# ESP32-S3_module.net
KiCad netlist of a schematic drawn in Altium Designer
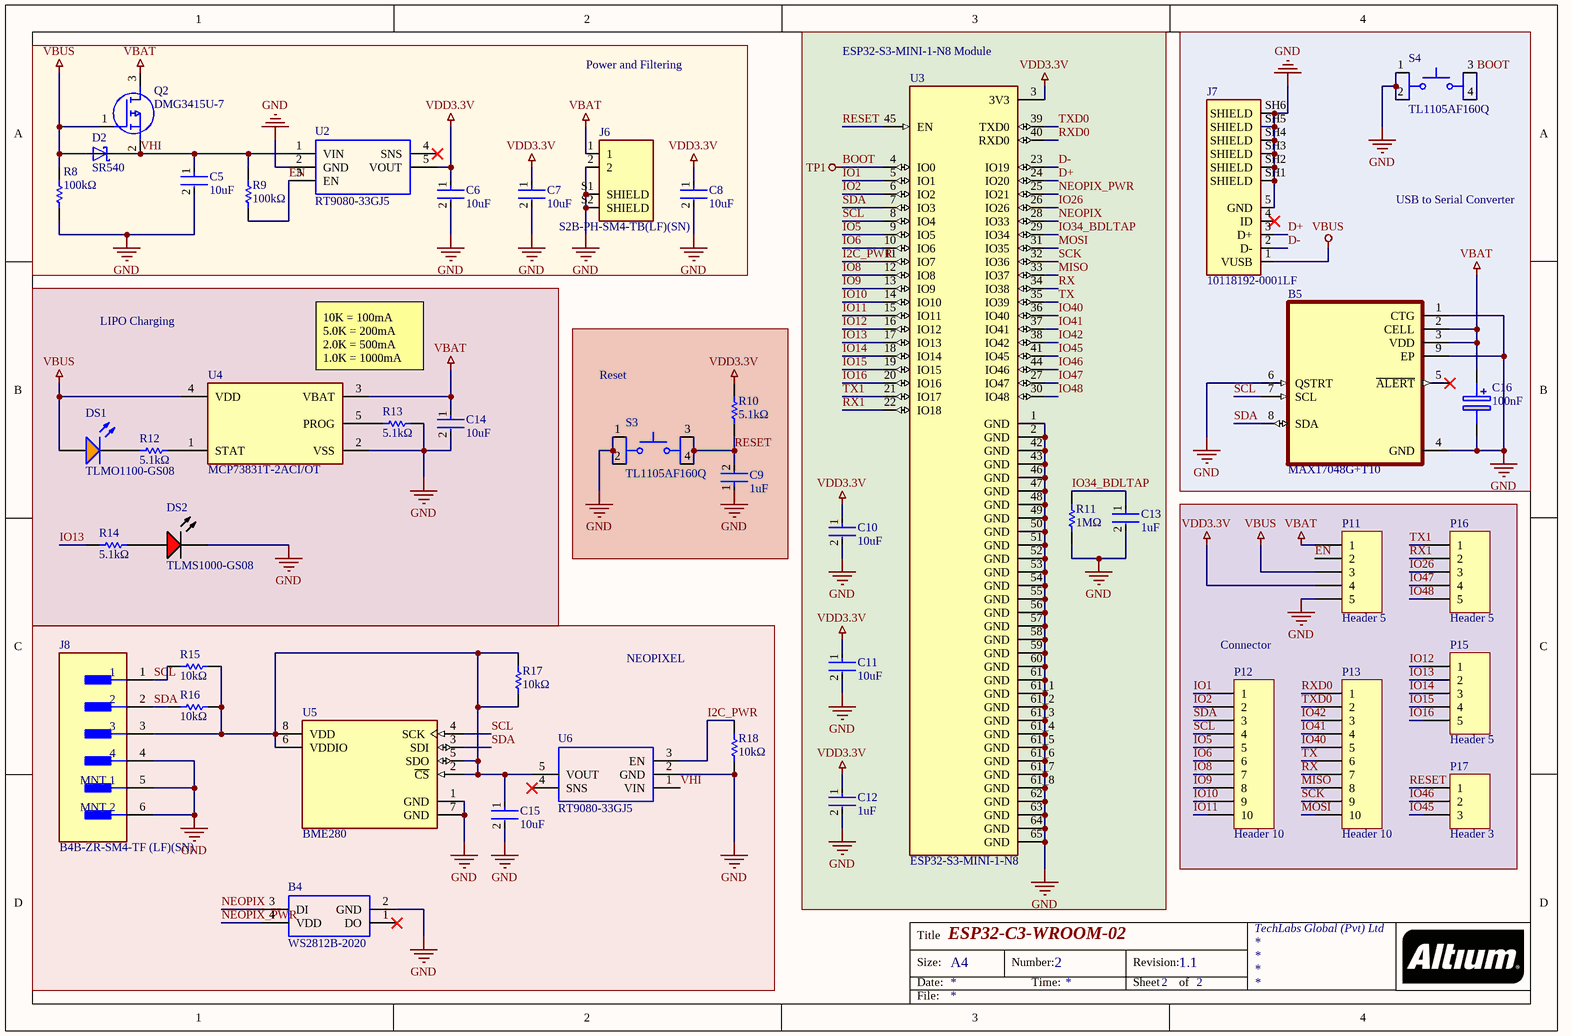
[diagram p0: ESP32-S3 module.SchDoc]

(export (version "E")
  (design (tool "Eeschema 10.0.6"))
  (components
    (comp (ref "B4")
      (value "WS2812B-2020")
      (footprint "WS2812B2020")
      (description "RGB SMD,2x2mm Light Emitting Diodes (LED) ROHS")
      (fields (field (name "MANUFACTURER") "Worldsemi") (field (name "LCSC PART #") "C965555"))
      (libsource (lib "WS2812B-2020") (part "WS2812B-2020"))
    )
    (comp (ref "B5")
      (value "MAX17048G+T10")
      (footprint "MAX17048G+T10")
      (description "Polymer 1 DFN-8-EP(2x2) Battery Management ICs ROHS")
      (fields
        (field (name "LCSC PART #") "C2682616")
        (field (name "MANUFACTURER") "Analog Devices Inc./Maxim Integrated")
      )
      (libsource (lib "MAX17048G+T10") (part "MAX17048G+T10"))
    )
    (comp (ref "C5")
      (value "10uF")
      (footprint "FP-CL10-IPC_C")
      (description "X5R 25V 10uF ±20% 0603 Multilayer Ceramic Capacitors MLCC - SMD/SMT ROHS")
      (fields (field (name "MFR. PART #") "CL10A106MA8NRNC") (field (name "LCSC PART #") "C96446"))
      (libsource (lib "Altium Content Vault") (part "b4654b650e69147ec39a6b967a45e02"))
    )
    (comp (ref "C6")
      (value "10uF")
      (footprint "FP-CL10-IPC_C")
      (description "X5R 25V 10uF ±20% 0603 Multilayer Ceramic Capacitors MLCC - SMD/SMT ROHS")
      (fields (field (name "MFR. PART #") "CL10A106MA8NRNC") (field (name "LCSC PART #") "C96446"))
      (libsource (lib "Altium Content Vault") (part "b4654b650e69147ec39a6b967a45e02"))
    )
    (comp (ref "C7")
      (value "10uF")
      (footprint "FP-CL10-IPC_C")
      (description "X5R 25V 10uF ±20% 0603 Multilayer Ceramic Capacitors MLCC - SMD/SMT ROHS")
      (fields (field (name "MFR. PART #") "CL10A106MA8NRNC") (field (name "LCSC PART #") "C96446"))
      (libsource (lib "Altium Content Vault") (part "b4654b650e69147ec39a6b967a45e02"))
    )
    (comp (ref "C8")
      (value "10uF")
      (footprint "FP-CL10-IPC_C")
      (description "X5R 25V 10uF ±20% 0603 Multilayer Ceramic Capacitors MLCC - SMD/SMT ROHS")
      (fields (field (name "MFR. PART #") "CL10A106MA8NRNC") (field (name "LCSC PART #") "C96446"))
      (libsource (lib "Altium Content Vault") (part "b4654b650e69147ec39a6b967a45e02"))
    )
    (comp (ref "C9")
      (value "1uF")
      (footprint "FP-CL10-IPC_A")
      (description "X5R 1uF 16V ±10% 0603 Multilayer Ceramic Capacitors MLCC - SMD/SMT ROHS")
      (fields (field (name "MANUFACTURER") "Samsung Electro-Mechanics") (field (name "LCSC PART #") "C1592"))
      (libsource (lib "Altium Content Vault") (part "b4654b650e69147ec39a6b967a45e02"))
    )
    (comp (ref "C10")
      (value "10uF")
      (footprint "FP-CL10-IPC_C")
      (description "X5R 25V 10uF ±20% 0603 Multilayer Ceramic Capacitors MLCC - SMD/SMT ROHS")
      (fields (field (name "MFR. PART #") "CL10A106MA8NRNC") (field (name "LCSC PART #") "C96446"))
      (libsource (lib "Altium Content Vault") (part "b4654b650e69147ec39a6b967a45e02"))
    )
    (comp (ref "C11")
      (value "10uF")
      (footprint "FP-CL10-IPC_C")
      (description "X5R 25V 10uF ±20% 0603 Multilayer Ceramic Capacitors MLCC - SMD/SMT ROHS")
      (fields (field (name "MFR. PART #") "CL10A106MA8NRNC") (field (name "LCSC PART #") "C96446"))
      (libsource (lib "Altium Content Vault") (part "b4654b650e69147ec39a6b967a45e02"))
    )
    (comp (ref "C12")
      (value "1uF")
      (footprint "FP-CL10-IPC_A")
      (description "X5R 1uF 16V ±10% 0603 Multilayer Ceramic Capacitors MLCC - SMD/SMT ROHS")
      (fields (field (name "LCSC PART #") "C1592") (field (name "MFR. PART #") "CL10A105KO8NNNC"))
      (libsource (lib "Altium Content Vault") (part "b4654b650e69147ec39a6b967a45e02"))
    )
    (comp (ref "C13")
      (value "1uF")
      (footprint "FP-CL10-IPC_A")
      (description "X5R 1uF 16V ±10% 0603 Multilayer Ceramic Capacitors MLCC - SMD/SMT ROHS")
      (fields (field (name "LCSC PART #") "C1592") (field (name "MFR. PART #") "CL10A105KO8NNNC"))
      (libsource (lib "Altium Content Vault") (part "b4654b650e69147ec39a6b967a45e02"))
    )
    (comp (ref "C14")
      (value "10uF")
      (footprint "FP-CL10-IPC_C")
      (description "X5R 25V 10uF ±20% 0603 Multilayer Ceramic Capacitors MLCC - SMD/SMT ROHS")
      (fields (field (name "MFR. PART #") "CL10A106MA8NRNC") (field (name "LCSC PART #") "C96446"))
      (libsource (lib "Altium Content Vault") (part "b4654b650e69147ec39a6b967a45e02"))
    )
    (comp (ref "C15")
      (value "10uF")
      (footprint "FP-CL10-IPC_C")
      (description "X5R 25V 10uF ±20% 0603 Multilayer Ceramic Capacitors MLCC - SMD/SMT ROHS")
      (fields (field (name "MFR. PART #") "CL10A106MA8NRNC") (field (name "LCSC PART #") "C96446"))
      (libsource (lib "Altium Content Vault") (part "b4654b650e69147ec39a6b967a45e02"))
    )
    (comp (ref "C16")
      (value "100nF")
      (footprint "T491A")
      (description "100nF 35V 20Ω@100kHz ±10% CASE-A-3216 Tantalum Capacitors ROHS")
      (fields (field (name "LCSC PART #") "C122257") (field (name "MFR. PART #") "T491A104K035AT"))
      (libsource (lib "T491A104K035AT") (part "T491A104K035AT"))
    )
    (comp (ref "D2")
      (value "SR540")
      (footprint "MBR540-DO-201AD")
      (description "40V 550mV@5A 5A DO-201AD Schottky Barrier Diodes (SBD) ROHS")
      (fields (field (name "MANUFACTURER") "DIYI Elec Tech") (field (name "LCSC PART #") "C129837"))
      (libsource (lib "MBR540-DO-201AD") (part "MBR540-DO-201AD"))
    )
    (comp (ref "DS1")
      (value "TLMO1100-GS08")
      (footprint "VISH-TLMX1100-2_V")
      (description "0603 Light Emitting Diodes (LED) ROHS")
      (fields (field (name "MANUFACTURER") "Vishay Intertech") (field (name "LCSC PART #") "C3148192"))
      (libsource (lib "Altium Content Vault") (part "LED-ORANGE-AK-2"))
    )
    (comp (ref "DS2")
      (value "TLMS1000-GS08")
      (footprint "VISH-TLMS1000_V")
      (description "Red 0603 Light Emitting Diodes (LED) ROHS")
      (fields (field (name "LCSC PART #") "C241893") (field (name "MANUFACTURER") "Vishay Intertech"))
      (libsource (lib "Altium Content Vault") (part "LED-RED-AK-2"))
    )
    (comp (ref "J6")
      (value "S2B-PH-SM4-TB(LF)(SN)")
      (footprint "JST_S2B-PH-SM4-TB(LF)(SN)")
      (fields (field (name "MANUFACTURER") "JST Sales America") (field (name "LCSC PART #") "C295747"))
      (libsource (lib "S2B-PH-SM4-TB(LF)(SN)") (part "S2B-PH-SM4-TB(LF)(SN)"))
    )
    (comp (ref "J7")
      (value "10118192-0001LF")
      (footprint "AMPHENOL_10118192-0001LF")
      (description "Single Port 5 Contact Horizontal Right Angle Shielded Micro B USB 2.0 Connector")
      (fields (field (name "LCSC PART #") "C132564") (field (name "MANUFACTURER") "Amphenol ICC"))
      (libsource (lib "10118192-0001LF") (part "10118192-0001LF"))
    )
    (comp (ref "J8")
      (value "B4B-ZR-SM4-TF (LF)(SN)")
      (footprint "FP-B4B-ZR-SM4-TF_LF_SN-MFG")
      (description "1x4P 1 1.5mm 4 Brass SMD,P=1.5mm Wire To Board / Wire To Wire Connector ROHS")
      (fields
        (field (name "MANUFACTURER") "JST Sales America")
        (field (name "MFR. PART #") "B4B-ZR-SM4-TF(LF)(SN)")
      )
      (libsource (lib "Altium Content Vault") (part "8e3688c4b118bffc0dd9b7401e414ba"))
    )
    (comp (ref "P11")
      (value "Header 5")
      (footprint "HDR1X5")
      (description "Header, 5-Pin")
      (fields (field (name "PUBLISHER") "Altium Limited"))
      (libsource (lib "Miscellaneous Connectors") (part "Header 5"))
    )
    (comp (ref "P12")
      (value "Header 10")
      (footprint "HDR1X10")
      (description "Header, 10-Pin")
      (fields (field (name "PUBLISHER") "Altium Limited"))
      (libsource (lib "Miscellaneous Connectors") (part "Header 10"))
    )
    (comp (ref "P13")
      (value "Header 10")
      (footprint "HDR1X10")
      (description "Header, 10-Pin")
      (fields (field (name "PUBLISHER") "Altium Limited"))
      (libsource (lib "Miscellaneous Connectors") (part "Header 10"))
    )
    (comp (ref "P15")
      (value "Header 5")
      (footprint "HDR1X5")
      (description "Header, 5-Pin")
      (fields (field (name "PUBLISHER") "Altium Limited"))
      (libsource (lib "Miscellaneous Connectors") (part "Header 5"))
    )
    (comp (ref "P16")
      (value "Header 5")
      (footprint "HDR1X5")
      (description "Header, 5-Pin")
      (fields (field (name "PUBLISHER") "Altium Limited"))
      (libsource (lib "Miscellaneous Connectors") (part "Header 5"))
    )
    (comp (ref "P17")
      (value "Header 3")
      (footprint "HDR1X3")
      (description "Header, 3-Pin")
      (fields (field (name "PUBLISHER") "Altium Limited"))
      (libsource (lib "Miscellaneous Connectors") (part "Header 3"))
    )
    (comp (ref "Q2")
      (value "DMG3415U-7")
      (footprint "SOT96P240X120-3N")
      (description "20V 4A 39mΩ@4.5V,4A 900mW P Channel SOT-23 MOSFETs ROHS")
      (fields (field (name "MANUFACTURER") "Diodes Incorporated") (field (name "LCSC PART #") "C96616"))
      (libsource (lib "DMG3415U-7") (part "DMG3415U-7"))
    )
    (comp (ref "R8")
      (value "100kΩ")
      (footprint "RESC1005X40X25NL05T10")
      (description "62.5mW 100kΩ ±1% Thick Film Resistors 0402 Chip Resistor - Surface Mount ROHS")
      (fields (field (name "MFR. PART #") "RC0402FR-07100KL") (field (name "MANUFACTURER") "YAGEO"))
      (libsource (lib "Altium Content Vault") (part "RES"))
    )
    (comp (ref "R9")
      (value "100kΩ")
      (footprint "RESC1005X40X25NL05T10")
      (description "62.5mW 100kΩ ±1% Thick Film Resistors 0402 Chip Resistor - Surface Mount ROHS")
      (fields (field (name "MFR. PART #") "RC0402FR-07100KL") (field (name "MANUFACTURER") "YAGEO"))
      (libsource (lib "Altium Content Vault") (part "RES"))
    )
    (comp (ref "R10")
      (value "5.1kΩ")
      (footprint "RESC1005X40X25NL05T10")
      (description "62.5mW Thick Film Resistors ±1% 5.1kΩ 0402 Chip Resistor - Surface Mount ROHS")
      (fields (field (name "MFR. PART #") "RC0402FR-075K1L") (field (name "MANUFACTURER") "YAGEO"))
      (libsource (lib "Altium Content Vault") (part "RES"))
    )
    (comp (ref "R11")
      (value "1MΩ")
      (footprint "RESC1005X40X25NL05T10")
      (description "62.5mW Thick Film Resistors ±1% 1MΩ 0402 Chip Resistor - Surface Mount ROHS")
      (fields (field (name "MFR. PART #") "RC0402FR-071ML") (field (name "LCSC PART #") "C138033"))
      (libsource (lib "Altium Content Vault") (part "RES"))
    )
    (comp (ref "R12")
      (value "5.1kΩ")
      (footprint "RESC1005X40X25NL05T10")
      (description "62.5mW Thick Film Resistors ±1% 5.1kΩ 0402 Chip Resistor - Surface Mount ROHS")
      (fields (field (name "MFR. PART #") "RC0402FR-075K1L") (field (name "MANUFACTURER") "YAGEO"))
      (libsource (lib "Altium Content Vault") (part "RES"))
    )
    (comp (ref "R13")
      (value "5.1kΩ")
      (footprint "RESC1005X40X25NL05T10")
      (description "62.5mW Thick Film Resistors ±1% 5.1kΩ 0402 Chip Resistor - Surface Mount ROHS")
      (fields (field (name "MFR. PART #") "RC0402FR-075K1L") (field (name "MANUFACTURER") "YAGEO"))
      (libsource (lib "Altium Content Vault") (part "RES"))
    )
    (comp (ref "R14")
      (value "5.1kΩ")
      (footprint "RESC1005X40X25NL05T10")
      (description "62.5mW Thick Film Resistors ±1% 5.1kΩ 0402 Chip Resistor - Surface Mount ROHS")
      (fields (field (name "MFR. PART #") "RC0402FR-075K1L") (field (name "MANUFACTURER") "YAGEO"))
      (libsource (lib "Altium Content Vault") (part "RES"))
    )
    (comp (ref "R15")
      (value "10kΩ")
      (footprint "RESC1005X40X25LL05T10")
      (description "10kΩ Thick Film Resistors 62.5mW ±1% 0402 Chip Resistor - Surface Mount ROHS")
      (fields (field (name "MFR. PART #") "RC0402FR-0710KL") (field (name "MANUFACTURER") "YAGEO"))
      (libsource (lib "Altium Content Vault") (part "RES"))
    )
    (comp (ref "R16")
      (value "10kΩ")
      (footprint "RESC1005X40X25LL05T10")
      (description "10kΩ Thick Film Resistors 62.5mW ±1% 0402 Chip Resistor - Surface Mount ROHS")
      (fields (field (name "MFR. PART #") "RC0402FR-0710KL") (field (name "MANUFACTURER") "YAGEO"))
      (libsource (lib "Altium Content Vault") (part "RES"))
    )
    (comp (ref "R17")
      (value "10kΩ")
      (footprint "RESC1005X40X25LL05T10")
      (description "10kΩ Thick Film Resistors 62.5mW ±1% 0402 Chip Resistor - Surface Mount ROHS")
      (fields (field (name "MFR. PART #") "RC0402FR-0710KL") (field (name "MANUFACTURER") "YAGEO"))
      (libsource (lib "Altium Content Vault") (part "RES"))
    )
    (comp (ref "R18")
      (value "10kΩ")
      (footprint "RESC1005X40X25LL05T10")
      (description "10kΩ Thick Film Resistors 62.5mW ±1% 0402 Chip Resistor - Surface Mount ROHS")
      (fields (field (name "MFR. PART #") "RC0402FR-0710KL") (field (name "MANUFACTURER") "YAGEO"))
      (libsource (lib "Altium Content Vault") (part "RES"))
    )
    (comp (ref "S3")
      (value "TL1105AF160Q")
      (footprint "TL1105AF160Q")
      (description "6mm 1.4mm Round Button 50mA Straight 6mm SPST 12V Plugin,6x6mm Tactile Switches ROHS")
      (fields (field (name "MANUFACTURER") "E-Switch") (field (name "LCSC PART #") "C273465"))
      (libsource (lib "TL1105AF160Q") (part "TL1105AF160Q"))
    )
    (comp (ref "S4")
      (value "TL1105AF160Q")
      (footprint "TL1105AF160Q")
      (description "6mm 1.4mm Round Button 50mA Straight 6mm SPST 12V Plugin,6x6mm Tactile Switches ROHS")
      (fields (field (name "MANUFACTURER") "E-Switch") (field (name "LCSC PART #") "C273465"))
      (libsource (lib "TL1105AF160Q") (part "TL1105AF160Q"))
    )
    (comp (ref "U2")
      (value "RT9080-33GJ5")
      (footprint "SOT94P280X100-5N")
      (description "TSOT-23-5 Linear Voltage Regulators (LDO) ROHS")
      (fields (field (name "MANUFACTURER") "Richtek Tech") (field (name "LCSC PART #") "C841192"))
      (libsource (lib "RT9080-33GJ5") (part "RT9080-33GJ5"))
    )
    (comp (ref "U3")
      (value "ESP32-S3-MINI-1-N8")
      (footprint "XCVR_ESP32-S3-MINI-1-N8")
      (description "Bluetooth, WiFi 802.11b/g/n, Bluetooth v5.0 Transceiver Module 2.4GHz PCB Trace Surface Mount")
      (fields (field (name "MANUFACTURER") "Espressif Systems") (field (name "LCSC PART #") "C2913206"))
      (libsource (lib "ESP32-S3-MINI-1-N8") (part "U?"))
    )
    (comp (ref "U4")
      (value "MCP73831T-2ACI/OT")
      (footprint "FP-C04-091-OT-IPC_B")
      (description "SOT-23-5 Battery Management ICs ROHS")
      (fields (field (name "LCSC PART #") "C424093") (field (name "MANUFACTURER") "Microchip Tech"))
      (libsource (lib "Altium Content Vault") (part "61f5a3bb3429d9e0caadea342aa3b19"))
    )
    (comp (ref "U5")
      (value "BME280")
      (footprint "FP-BME280-MFG")
      (description "LGA-8 Temperature and Humidity Sensor ROHS")
      (fields (field (name "LCSC PART #") "C92489") (field (name "MANUFACTURER") "Bosch Sensortec"))
      (libsource (lib "Altium Content Vault") (part "d58e2f6669bc67e6a2bc6a28610ca79"))
    )
    (comp (ref "U6")
      (value "RT9080-33GJ5")
      (footprint "SOT94P280X100-5N")
      (description "TSOT-23-5 Linear Voltage Regulators (LDO) ROHS")
      (fields (field (name "MANUFACTURER") "Richtek Tech") (field (name "LCSC PART #") "C841192"))
      (libsource (lib "RT9080-33GJ5") (part "RT9080-33GJ5"))
    )
  )
  (nets
    (net (code "1") (name "/D+") (class "Default")
      (node (ref "J7") (pin "3") (pinfunction "D+_3") (pintype "passive"))
      (node (ref "U3") (pin "24") (pinfunction "IO20_24") (pintype "bidirectional"))
    )
    (net (code "2") (name "/D-") (class "Default")
      (node (ref "J7") (pin "2") (pinfunction "D-_2") (pintype "passive"))
      (node (ref "U3") (pin "23") (pinfunction "IO19_23") (pintype "bidirectional"))
    )
    (net (code "3") (name "/EN") (class "Default")
      (node (ref "P11") (pin "2") (pinfunction "2_2") (pintype "passive"))
      (node (ref "R9") (pin "2") (pinfunction "2_2") (pintype "passive"))
      (node (ref "U2") (pin "3") (pinfunction "EN_3") (pintype "passive"))
    )
    (net (code "4") (name "/I2C_PWR") (class "Default")
      (node (ref "R18") (pin "2") (pinfunction "2_2") (pintype "passive"))
      (node (ref "U3") (pin "11") (pinfunction "IO7_11") (pintype "bidirectional"))
      (node (ref "U6") (pin "3") (pinfunction "EN_3") (pintype "passive"))
    )
    (net (code "5") (name "/IO1") (class "Default")
      (node (ref "P12") (pin "1") (pinfunction "1_1") (pintype "passive"))
      (node (ref "U3") (pin "5") (pinfunction "IO1_5") (pintype "bidirectional"))
    )
    (net (code "6") (name "/IO2") (class "Default")
      (node (ref "P12") (pin "2") (pinfunction "2_2") (pintype "passive"))
      (node (ref "U3") (pin "6") (pinfunction "IO2_6") (pintype "bidirectional"))
    )
    (net (code "7") (name "/IO5") (class "Default")
      (node (ref "P12") (pin "5") (pinfunction "5_5") (pintype "passive"))
      (node (ref "U3") (pin "9") (pinfunction "IO5_9") (pintype "bidirectional"))
    )
    (net (code "8") (name "/IO6") (class "Default")
      (node (ref "P12") (pin "6") (pinfunction "6_6") (pintype "passive"))
      (node (ref "U3") (pin "10") (pinfunction "IO6_10") (pintype "bidirectional"))
    )
    (net (code "9") (name "/IO8") (class "Default")
      (node (ref "P12") (pin "7") (pinfunction "7_7") (pintype "passive"))
      (node (ref "U3") (pin "12") (pinfunction "IO8_12") (pintype "bidirectional"))
    )
    (net (code "10") (name "/IO9") (class "Default")
      (node (ref "P12") (pin "8") (pinfunction "8_8") (pintype "passive"))
      (node (ref "U3") (pin "13") (pinfunction "IO9_13") (pintype "bidirectional"))
    )
    (net (code "11") (name "/IO10") (class "Default")
      (node (ref "P12") (pin "9") (pinfunction "9_9") (pintype "passive"))
      (node (ref "U3") (pin "14") (pinfunction "IO10_14") (pintype "bidirectional"))
    )
    (net (code "12") (name "/IO11") (class "Default")
      (node (ref "P12") (pin "10") (pinfunction "10_10") (pintype "passive"))
      (node (ref "U3") (pin "15") (pinfunction "IO11_15") (pintype "bidirectional"))
    )
    (net (code "13") (name "/IO12") (class "Default")
      (node (ref "P15") (pin "1") (pinfunction "1_1") (pintype "passive"))
      (node (ref "U3") (pin "16") (pinfunction "IO12_16") (pintype "bidirectional"))
    )
    (net (code "14") (name "/IO13") (class "Default")
      (node (ref "P15") (pin "2") (pinfunction "2_2") (pintype "passive"))
      (node (ref "R14") (pin "2") (pinfunction "2_2") (pintype "passive"))
      (node (ref "U3") (pin "17") (pinfunction "IO13_17") (pintype "bidirectional"))
    )
    (net (code "15") (name "/IO14") (class "Default")
      (node (ref "P15") (pin "3") (pinfunction "3_3") (pintype "passive"))
      (node (ref "U3") (pin "18") (pinfunction "IO14_18") (pintype "bidirectional"))
    )
    (net (code "16") (name "/IO15") (class "Default")
      (node (ref "P15") (pin "4") (pinfunction "4_4") (pintype "passive"))
      (node (ref "U3") (pin "19") (pinfunction "IO15_19") (pintype "bidirectional"))
    )
    (net (code "17") (name "/IO16") (class "Default")
      (node (ref "P15") (pin "5") (pinfunction "5_5") (pintype "passive"))
      (node (ref "U3") (pin "20") (pinfunction "IO16_20") (pintype "bidirectional"))
    )
    (net (code "18") (name "/IO26") (class "Default")
      (node (ref "P16") (pin "3") (pinfunction "3_3") (pintype "passive"))
      (node (ref "U3") (pin "26") (pinfunction "IO26_26") (pintype "bidirectional"))
    )
    (net (code "19") (name "/IO34_BDLTAP") (class "Default")
      (node (ref "C13") (pin "1") (pinfunction "1_1") (pintype "passive"))
      (node (ref "R11") (pin "2") (pinfunction "2_2") (pintype "passive"))
      (node (ref "U3") (pin "29") (pinfunction "IO34_29") (pintype "bidirectional"))
    )
    (net (code "20") (name "/IO40") (class "Default")
      (node (ref "P13") (pin "5") (pinfunction "5_5") (pintype "passive"))
      (node (ref "U3") (pin "36") (pinfunction "IO40_36") (pintype "bidirectional"))
    )
    (net (code "21") (name "/IO41") (class "Default")
      (node (ref "P13") (pin "4") (pinfunction "4_4") (pintype "passive"))
      (node (ref "U3") (pin "37") (pinfunction "IO41_37") (pintype "bidirectional"))
    )
    (net (code "22") (name "/IO42") (class "Default")
      (node (ref "P13") (pin "3") (pinfunction "3_3") (pintype "passive"))
      (node (ref "U3") (pin "38") (pinfunction "IO42_38") (pintype "bidirectional"))
    )
    (net (code "23") (name "/IO45") (class "Default")
      (node (ref "P17") (pin "3") (pinfunction "3_3") (pintype "passive"))
      (node (ref "U3") (pin "41") (pinfunction "IO45_41") (pintype "bidirectional"))
    )
    (net (code "24") (name "/IO46") (class "Default")
      (node (ref "P17") (pin "2") (pinfunction "2_2") (pintype "passive"))
      (node (ref "U3") (pin "44") (pinfunction "IO46_44") (pintype "bidirectional"))
    )
    (net (code "25") (name "/IO47") (class "Default")
      (node (ref "P16") (pin "4") (pinfunction "4_4") (pintype "passive"))
      (node (ref "U3") (pin "27") (pinfunction "IO47_27") (pintype "bidirectional"))
    )
    (net (code "26") (name "/IO48") (class "Default")
      (node (ref "P16") (pin "5") (pinfunction "5_5") (pintype "passive"))
      (node (ref "U3") (pin "30") (pinfunction "IO48_30") (pintype "bidirectional"))
    )
    (net (code "27") (name "/MISO") (class "Default")
      (node (ref "P13") (pin "8") (pinfunction "8_8") (pintype "passive"))
      (node (ref "U3") (pin "33") (pinfunction "IO37_33") (pintype "bidirectional"))
    )
    (net (code "28") (name "/MOSI") (class "Default")
      (node (ref "P13") (pin "10") (pinfunction "10_10") (pintype "passive"))
      (node (ref "U3") (pin "31") (pinfunction "IO35_31") (pintype "bidirectional"))
    )
    (net (code "29") (name "/NEOPIX") (class "Default")
      (node (ref "B4") (pin "3") (pinfunction "DI_3") (pintype "passive"))
      (node (ref "U3") (pin "28") (pinfunction "IO33_28") (pintype "bidirectional"))
    )
    (net (code "30") (name "/NEOPIX_PWR") (class "Default")
      (node (ref "B4") (pin "4") (pinfunction "VDD_4") (pintype "passive"))
      (node (ref "U3") (pin "25") (pinfunction "IO21_25") (pintype "bidirectional"))
    )
    (net (code "31") (name "/RESET") (class "Default")
      (node (ref "C9") (pin "2") (pinfunction "2_2") (pintype "passive"))
      (node (ref "P17") (pin "1") (pinfunction "1_1") (pintype "passive"))
      (node (ref "R10") (pin "1") (pinfunction "1_1") (pintype "passive"))
      (node (ref "S3") (pin "3") (pinfunction "3_3") (pintype "passive"))
      (node (ref "S3") (pin "4") (pinfunction "4_4") (pintype "passive"))
      (node (ref "U3") (pin "45") (pinfunction "EN_45") (pintype "input"))
    )
    (net (code "32") (name "/RX") (class "Default")
      (node (ref "P13") (pin "7") (pinfunction "7_7") (pintype "passive"))
      (node (ref "U3") (pin "34") (pinfunction "IO38_34") (pintype "bidirectional"))
    )
    (net (code "33") (name "/RX1") (class "Default")
      (node (ref "P16") (pin "2") (pinfunction "2_2") (pintype "passive"))
      (node (ref "U3") (pin "22") (pinfunction "IO18_22") (pintype "bidirectional"))
    )
    (net (code "34") (name "/RXD0") (class "Default")
      (node (ref "P13") (pin "1") (pinfunction "1_1") (pintype "passive"))
      (node (ref "U3") (pin "40") (pinfunction "RXD0_40") (pintype "bidirectional"))
    )
    (net (code "35") (name "/SCK") (class "Default")
      (node (ref "P13") (pin "9") (pinfunction "9_9") (pintype "passive"))
      (node (ref "U3") (pin "32") (pinfunction "IO36_32") (pintype "bidirectional"))
    )
    (net (code "36") (name "/SCL") (class "Default")
      (node (ref "B5") (pin "7") (pinfunction "SCL_7") (pintype "input"))
      (node (ref "J8") (pin "1") (pinfunction "1_1") (pintype "passive"))
      (node (ref "P12") (pin "4") (pinfunction "4_4") (pintype "passive"))
      (node (ref "R15") (pin "2") (pinfunction "2_2") (pintype "passive"))
      (node (ref "U3") (pin "8") (pinfunction "IO4_8") (pintype "bidirectional"))
      (node (ref "U5") (pin "4") (pinfunction "SCK_4") (pintype "input"))
    )
    (net (code "37") (name "/SDA") (class "Default")
      (node (ref "B5") (pin "8") (pinfunction "SDA_8") (pintype "bidirectional"))
      (node (ref "J8") (pin "2") (pinfunction "2_2") (pintype "passive"))
      (node (ref "P12") (pin "3") (pinfunction "3_3") (pintype "passive"))
      (node (ref "R16") (pin "2") (pinfunction "2_2") (pintype "passive"))
      (node (ref "U3") (pin "7") (pinfunction "IO3_7") (pintype "bidirectional"))
      (node (ref "U5") (pin "3") (pinfunction "SDI_3") (pintype "bidirectional"))
    )
    (net (code "38") (name "/TX") (class "Default")
      (node (ref "P13") (pin "6") (pinfunction "6_6") (pintype "passive"))
      (node (ref "U3") (pin "35") (pinfunction "IO39_35") (pintype "bidirectional"))
    )
    (net (code "39") (name "/TX1") (class "Default")
      (node (ref "P16") (pin "1") (pinfunction "1_1") (pintype "passive"))
      (node (ref "U3") (pin "21") (pinfunction "IO17_21") (pintype "bidirectional"))
    )
    (net (code "40") (name "/TXD0") (class "Default")
      (node (ref "P13") (pin "2") (pinfunction "2_2") (pintype "passive"))
      (node (ref "U3") (pin "39") (pinfunction "TXD0_39") (pintype "bidirectional"))
    )
    (net (code "41") (name "/VHI") (class "Default")
      (node (ref "C5") (pin "1") (pinfunction "1_1") (pintype "passive"))
      (node (ref "D2") (pin "C") (pinfunction "C_C") (pintype "passive"))
      (node (ref "Q2") (pin "2") (pinfunction "S_2") (pintype "passive"))
      (node (ref "R9") (pin "1") (pinfunction "1_1") (pintype "passive"))
      (node (ref "U2") (pin "1") (pinfunction "VIN_1") (pintype "passive"))
      (node (ref "U6") (pin "1") (pinfunction "VIN_1") (pintype "passive"))
    )
    (net (code "42") (name "GND") (class "Default")
      (node (ref "B4") (pin "2") (pinfunction "GND_2") (pintype "passive"))
      (node (ref "B5") (pin "1") (pinfunction "CTG_1") (pintype "power_in"))
      (node (ref "B5") (pin "4") (pinfunction "GND_4") (pintype "power_in"))
      (node (ref "B5") (pin "6") (pinfunction "QSTRT_6") (pintype "input"))
      (node (ref "B5") (pin "9") (pinfunction "EP_9") (pintype "power_in"))
      (node (ref "C10") (pin "2") (pinfunction "2_2") (pintype "passive"))
      (node (ref "C11") (pin "2") (pinfunction "2_2") (pintype "passive"))
      (node (ref "C12") (pin "2") (pinfunction "2_2") (pintype "passive"))
      (node (ref "C13") (pin "2") (pinfunction "2_2") (pintype "passive"))
      (node (ref "C14") (pin "2") (pinfunction "2_2") (pintype "passive"))
      (node (ref "C15") (pin "2") (pinfunction "2_2") (pintype "passive"))
      (node (ref "C16") (pin "2") (pinfunction "-_2") (pintype "passive"))
      (node (ref "C5") (pin "2") (pinfunction "2_2") (pintype "passive"))
      (node (ref "C6") (pin "2") (pinfunction "2_2") (pintype "passive"))
      (node (ref "C7") (pin "2") (pinfunction "2_2") (pintype "passive"))
      (node (ref "C8") (pin "2") (pinfunction "2_2") (pintype "passive"))
      (node (ref "C9") (pin "1") (pinfunction "1_1") (pintype "passive"))
      (node (ref "DS2") (pin "2") (pinfunction "K_2") (pintype "passive"))
      (node (ref "J6") (pin "2") (pinfunction "2_2") (pintype "passive"))
      (node (ref "J6") (pin "S1") (pinfunction "SHIELD_S1") (pintype "passive"))
      (node (ref "J6") (pin "S2") (pinfunction "SHIELD_S2") (pintype "passive"))
      (node (ref "J7") (pin "5") (pinfunction "GND_5") (pintype "passive"))
      (node (ref "J7") (pin "SH1") (pinfunction "SHIELD_SH1") (pintype "passive"))
      (node (ref "J7") (pin "SH2") (pinfunction "SHIELD_SH2") (pintype "passive"))
      (node (ref "J7") (pin "SH3") (pinfunction "SHIELD_SH3") (pintype "passive"))
      (node (ref "J7") (pin "SH4") (pinfunction "SHIELD_SH4") (pintype "passive"))
      (node (ref "J7") (pin "SH5") (pinfunction "SHIELD_SH5") (pintype "passive"))
      (node (ref "J7") (pin "SH6") (pinfunction "SHIELD_SH6") (pintype "passive"))
      (node (ref "J8") (pin "4") (pinfunction "4_4") (pintype "passive"))
      (node (ref "J8") (pin "5") (pinfunction "MNT_1_5") (pintype "passive"))
      (node (ref "J8") (pin "6") (pinfunction "MNT_2_6") (pintype "passive"))
      (node (ref "P11") (pin "5") (pinfunction "5_5") (pintype "passive"))
      (node (ref "R11") (pin "1") (pinfunction "1_1") (pintype "passive"))
      (node (ref "R13") (pin "1") (pinfunction "1_1") (pintype "passive"))
      (node (ref "R18") (pin "1") (pinfunction "1_1") (pintype "passive"))
      (node (ref "R8") (pin "1") (pinfunction "1_1") (pintype "passive"))
      (node (ref "S3") (pin "1") (pinfunction "1_1") (pintype "passive"))
      (node (ref "S3") (pin "2") (pinfunction "2_2") (pintype "passive"))
      (node (ref "S4") (pin "1") (pinfunction "1_1") (pintype "passive"))
      (node (ref "S4") (pin "2") (pinfunction "2_2") (pintype "passive"))
      (node (ref "U2") (pin "2") (pinfunction "GND_2") (pintype "passive"))
      (node (ref "U3") (pin "1") (pinfunction "GND_1") (pintype "power_in"))
      (node (ref "U3") (pin "2") (pinfunction "GND_2") (pintype "power_in"))
      (node (ref "U3") (pin "42") (pinfunction "GND_42") (pintype "power_in"))
      (node (ref "U3") (pin "43") (pinfunction "GND_43") (pintype "power_in"))
      (node (ref "U3") (pin "46") (pinfunction "GND_46") (pintype "power_in"))
      (node (ref "U3") (pin "47") (pinfunction "GND_47") (pintype "power_in"))
      (node (ref "U3") (pin "48") (pinfunction "GND_48") (pintype "power_in"))
      (node (ref "U3") (pin "49") (pinfunction "GND_49") (pintype "power_in"))
      (node (ref "U3") (pin "50") (pinfunction "GND_50") (pintype "power_in"))
      (node (ref "U3") (pin "51") (pinfunction "GND_51") (pintype "power_in"))
      (node (ref "U3") (pin "52") (pinfunction "GND_52") (pintype "power_in"))
      (node (ref "U3") (pin "53") (pinfunction "GND_53") (pintype "power_in"))
      (node (ref "U3") (pin "54") (pinfunction "GND_54") (pintype "power_in"))
      (node (ref "U3") (pin "55") (pinfunction "GND_55") (pintype "power_in"))
      (node (ref "U3") (pin "56") (pinfunction "GND_56") (pintype "power_in"))
      (node (ref "U3") (pin "57") (pinfunction "GND_57") (pintype "power_in"))
      (node (ref "U3") (pin "58") (pinfunction "GND_58") (pintype "power_in"))
      (node (ref "U3") (pin "59") (pinfunction "GND_59") (pintype "power_in"))
      (node (ref "U3") (pin "60") (pinfunction "GND_60") (pintype "power_in"))
      (node (ref "U3") (pin "61") (pinfunction "GND_61") (pintype "power_in"))
      (node (ref "U3") (pin "61_1") (pinfunction "GND_61_1") (pintype "power_in"))
      (node (ref "U3") (pin "61_2") (pinfunction "GND_61_2") (pintype "power_in"))
      (node (ref "U3") (pin "61_3") (pinfunction "GND_61_3") (pintype "power_in"))
      (node (ref "U3") (pin "61_4") (pinfunction "GND_61_4") (pintype "power_in"))
      (node (ref "U3") (pin "61_5") (pinfunction "GND_61_5") (pintype "power_in"))
      (node (ref "U3") (pin "61_6") (pinfunction "GND_61_6") (pintype "power_in"))
      (node (ref "U3") (pin "61_7") (pinfunction "GND_61_7") (pintype "power_in"))
      (node (ref "U3") (pin "61_8") (pinfunction "GND_61_8") (pintype "power_in"))
      (node (ref "U3") (pin "62") (pinfunction "GND_62") (pintype "power_in"))
      (node (ref "U3") (pin "63") (pinfunction "GND_63") (pintype "power_in"))
      (node (ref "U3") (pin "64") (pinfunction "GND_64") (pintype "power_in"))
      (node (ref "U3") (pin "65") (pinfunction "GND_65") (pintype "power_in"))
      (node (ref "U4") (pin "2") (pinfunction "VSS_2") (pintype "power_in"))
      (node (ref "U5") (pin "1") (pinfunction "GND_1") (pintype "power_in"))
      (node (ref "U5") (pin "7") (pinfunction "GND_7") (pintype "power_in"))
      (node (ref "U6") (pin "2") (pinfunction "GND_2") (pintype "passive"))
    )
    (net (code "43") (name "Net-(DS1-K)") (class "Default")
      (node (ref "DS1") (pin "2") (pinfunction "K_2") (pintype "passive"))
      (node (ref "R12") (pin "2") (pinfunction "2_2") (pintype "passive"))
    )
    (net (code "44") (name "Net-(DS2-A)") (class "Default")
      (node (ref "DS2") (pin "1") (pinfunction "A_1") (pintype "passive"))
      (node (ref "R14") (pin "1") (pinfunction "1_1") (pintype "passive"))
    )
    (net (code "45") (name "Net-(U4-PROG)") (class "Default")
      (node (ref "R13") (pin "2") (pinfunction "2_2") (pintype "passive"))
      (node (ref "U4") (pin "5") (pinfunction "PROG_5") (pintype "passive"))
    )
    (net (code "46") (name "Net-(U4-STAT)") (class "Default")
      (node (ref "R12") (pin "1") (pinfunction "1_1") (pintype "passive"))
      (node (ref "U4") (pin "1") (pinfunction "STAT_1") (pintype "passive"))
    )
    (net (code "47") (name "Net-(U5-SDO)") (class "Default")
      (node (ref "C15") (pin "1") (pinfunction "1_1") (pintype "passive"))
      (node (ref "J8") (pin "3") (pinfunction "3_3") (pintype "passive"))
      (node (ref "R15") (pin "1") (pinfunction "1_1") (pintype "passive"))
      (node (ref "R16") (pin "1") (pinfunction "1_1") (pintype "passive"))
      (node (ref "R17") (pin "1") (pinfunction "1_1") (pintype "passive"))
      (node (ref "R17") (pin "2") (pinfunction "2_2") (pintype "passive"))
      (node (ref "U5") (pin "2") (pinfunction "~{CS}_2") (pintype "input"))
      (node (ref "U5") (pin "5") (pinfunction "SDO_5") (pintype "bidirectional"))
      (node (ref "U5") (pin "6") (pinfunction "VDDIO_6") (pintype "power_in"))
      (node (ref "U5") (pin "8") (pinfunction "VDD_8") (pintype "power_in"))
      (node (ref "U6") (pin "5") (pinfunction "VOUT_5") (pintype "passive"))
    )
    (net (code "48") (name "TP1") (class "Default")
      (node (ref "S4") (pin "3") (pinfunction "3_3") (pintype "passive"))
      (node (ref "S4") (pin "4") (pinfunction "4_4") (pintype "passive"))
      (node (ref "U3") (pin "4") (pinfunction "IO0_4") (pintype "bidirectional"))
    )
    (net (code "49") (name "VBAT") (class "Default")
      (node (ref "B5") (pin "2") (pinfunction "CELL_2") (pintype "power_in"))
      (node (ref "B5") (pin "3") (pinfunction "VDD_3") (pintype "power_in"))
      (node (ref "C14") (pin "1") (pinfunction "1_1") (pintype "passive"))
      (node (ref "C16") (pin "1") (pinfunction "+_1") (pintype "passive"))
      (node (ref "J6") (pin "1") (pinfunction "1_1") (pintype "passive"))
      (node (ref "P11") (pin "1") (pinfunction "1_1") (pintype "passive"))
      (node (ref "Q2") (pin "3") (pinfunction "D_3") (pintype "passive"))
      (node (ref "U4") (pin "3") (pinfunction "VBAT_3") (pintype "power_in"))
    )
    (net (code "50") (name "VBUS") (class "Default")
      (node (ref "D2") (pin "A") (pinfunction "A_A") (pintype "passive"))
      (node (ref "DS1") (pin "1") (pinfunction "A_1") (pintype "passive"))
      (node (ref "J7") (pin "1") (pinfunction "VUSB_1") (pintype "passive"))
      (node (ref "P11") (pin "3") (pinfunction "3_3") (pintype "passive"))
      (node (ref "Q2") (pin "1") (pinfunction "G_1") (pintype "passive"))
      (node (ref "R8") (pin "2") (pinfunction "2_2") (pintype "passive"))
      (node (ref "U4") (pin "4") (pinfunction "VDD_4") (pintype "power_in"))
    )
    (net (code "51") (name "VDD3.3V") (class "Default")
      (node (ref "C10") (pin "1") (pinfunction "1_1") (pintype "passive"))
      (node (ref "C11") (pin "1") (pinfunction "1_1") (pintype "passive"))
      (node (ref "C12") (pin "1") (pinfunction "1_1") (pintype "passive"))
      (node (ref "C6") (pin "1") (pinfunction "1_1") (pintype "passive"))
      (node (ref "C7") (pin "1") (pinfunction "1_1") (pintype "passive"))
      (node (ref "C8") (pin "1") (pinfunction "1_1") (pintype "passive"))
      (node (ref "P11") (pin "4") (pinfunction "4_4") (pintype "passive"))
      (node (ref "R10") (pin "2") (pinfunction "2_2") (pintype "passive"))
      (node (ref "U2") (pin "5") (pinfunction "VOUT_5") (pintype "passive"))
      (node (ref "U3") (pin "3") (pinfunction "3V3_3") (pintype "power_in"))
    )
    (net (code "52") (name "unconnected-(B4-DO-Pad1)") (class "Default")
      (node (ref "B4") (pin "1") (pinfunction "DO_1") (pintype "passive+no_connect"))
    )
    (net (code "53") (name "unconnected-(B5-~{ALERT}-Pad5)") (class "Default")
      (node (ref "B5") (pin "5") (pinfunction "~{ALERT}_5") (pintype "output+no_connect"))
    )
    (net (code "54") (name "unconnected-(J7-ID-Pad4)") (class "Default")
      (node (ref "J7") (pin "4") (pinfunction "ID_4") (pintype "passive+no_connect"))
    )
    (net (code "55") (name "unconnected-(U2-SNS-Pad4)") (class "Default")
      (node (ref "U2") (pin "4") (pinfunction "SNS_4") (pintype "passive+no_connect"))
    )
    (net (code "56") (name "unconnected-(U6-SNS-Pad4)") (class "Default")
      (node (ref "U6") (pin "4") (pinfunction "SNS_4") (pintype "passive+no_connect"))
    )
  )
)
